# SmartSensorWifi.net
KiCad netlist of a schematic drawn in EAGLE
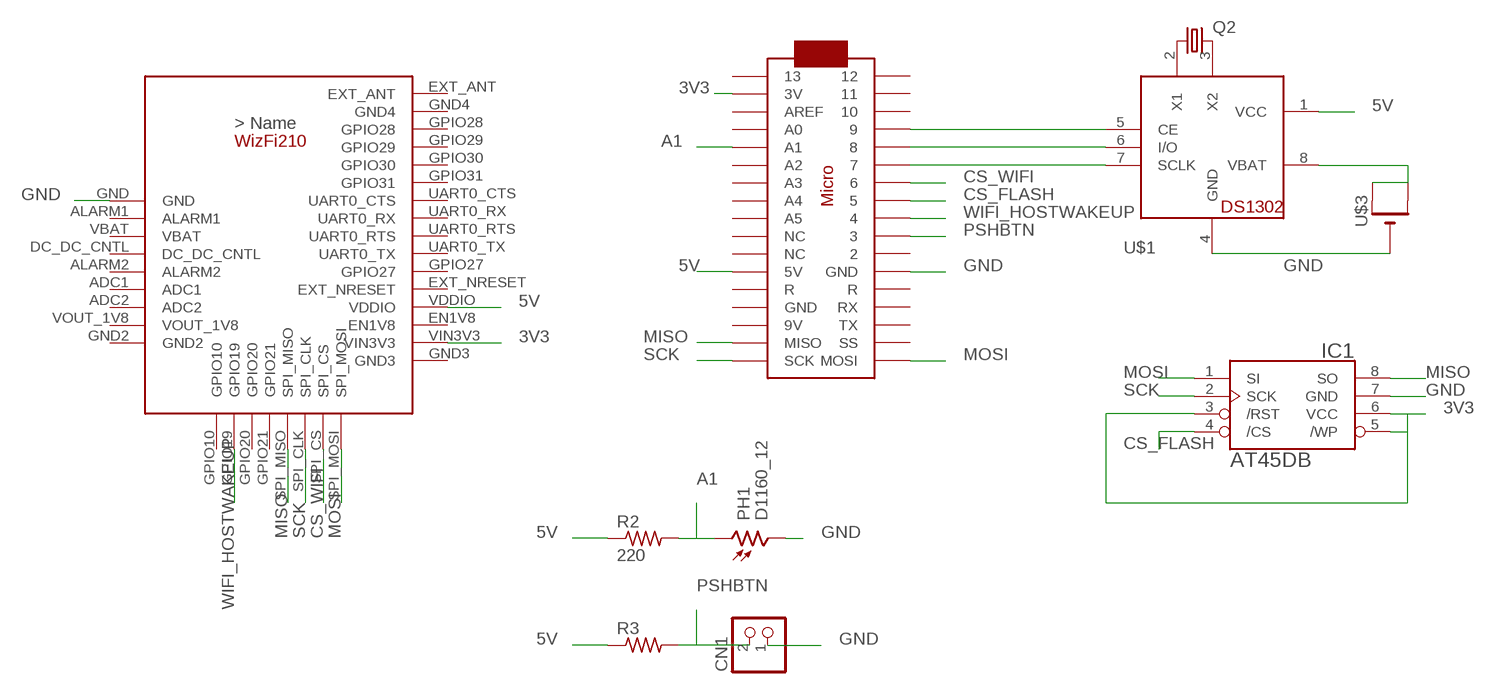
[diagram p0: schematic, sheet 1]

(export (version "E")
  (design (tool "Eeschema 10.0.6"))
  (components
    (comp (ref "CN1")
      (value "JST_2PIN-THM")
      (footprint "eagle-import:JST-PH-2-THM")
      (libsource (lib "eagle-import") (part "JST_2PIN-THM"))
    )
    (comp (ref "IC1")
      (value "AT45DB-S")
      (footprint "eagle-import:SOIC8_208MIL")
      (libsource (lib "eagle-import") (part "AT45DB-S"))
    )
    (comp (ref "PH1")
      (value "D1160_12")
      (footprint "eagle-import:D11XX")
      (libsource (lib "eagle-import") (part "D1160_12"))
    )
    (comp (ref "Q2")
      (value "CRYSTALTC38H")
      (footprint "eagle-import:TC38H")
      (libsource (lib "eagle-import") (part "CRYSTALTC38H"))
    )
    (comp (ref "R2")
      (value "220")
      (footprint "eagle-import:0207_12")
      (libsource (lib "eagle-import") (part "R-US_0207/12"))
    )
    (comp (ref "R3")
      (value "R-US_0207/12")
      (footprint "eagle-import:0207_12")
      (libsource (lib "eagle-import") (part "R-US_0207/12"))
    )
    (comp (ref "U$1")
      (value "DS1302")
      (footprint "eagle-import:DIL08-ROUND")
      (libsource (lib "eagle-import") (part "DS1302"))
    )
    (comp (ref "U$2")
      (value "ARDUINOMICRO")
      (footprint "eagle-import:ARDUINOMICRO")
      (libsource (lib "eagle-import") (part "ARDUINOMICRO"))
    )
    (comp (ref "U$3")
      (value "CR2032THM")
      (footprint "eagle-import:CR2032-THRU")
      (libsource (lib "eagle-import") (part "CR2032THM"))
    )
    (comp (ref "U$4")
      (value "WIZFISTACKED")
      (footprint "eagle-import:WIZFI210STACKABLE")
      (libsource (lib "eagle-import") (part "WIZFISTACKED"))
    )
  )
  (nets
    (net (code "1") (name "/3V3") (class "Default")
      (node (ref "IC1") (pin "3") (pinfunction "/RST_3") (pintype "input"))
      (node (ref "IC1") (pin "5") (pinfunction "/WP_5") (pintype "input"))
      (node (ref "IC1") (pin "6") (pinfunction "VCC_6") (pintype "power_in"))
      (node (ref "U$2") (pin "P$33") (pinfunction "3V_P$33") (pintype "bidirectional"))
      (node (ref "U$4") (pin "VIN3V3") (pinfunction "VIN3V3_VIN3V3") (pintype "power_in"))
    )
    (net (code "2") (name "/5V") (class "Default")
      (node (ref "R2") (pin "1") (pinfunction "1_1") (pintype "passive"))
      (node (ref "R3") (pin "1") (pinfunction "1_1") (pintype "passive"))
      (node (ref "U$1") (pin "1") (pinfunction "VCC_1") (pintype "power_in"))
      (node (ref "U$2") (pin "P$23") (pinfunction "5V_P$23") (pintype "bidirectional"))
      (node (ref "U$4") (pin "VDDIO") (pinfunction "VDDIO_VDDIO") (pintype "bidirectional"))
    )
    (net (code "3") (name "/A1") (class "Default")
      (node (ref "PH1") (pin "1") (pinfunction "1_1") (pintype "passive"))
      (node (ref "R2") (pin "2") (pinfunction "2_2") (pintype "passive"))
      (node (ref "U$2") (pin "P$30") (pinfunction "A1_P$30") (pintype "bidirectional"))
    )
    (net (code "4") (name "/CS_FLASH") (class "Default")
      (node (ref "IC1") (pin "4") (pinfunction "/CS_4") (pintype "input"))
      (node (ref "U$2") (pin "P$8") (pinfunction "5_P$8") (pintype "bidirectional"))
    )
    (net (code "5") (name "/CS_WIFI") (class "Default")
      (node (ref "U$2") (pin "P$7") (pinfunction "6_P$7") (pintype "bidirectional"))
      (node (ref "U$4") (pin "SPI_CS") (pinfunction "SPI_CS_SPI_CS") (pintype "input"))
    )
    (net (code "6") (name "/GND") (class "Default")
      (node (ref "CN1") (pin "1") (pinfunction "2_1") (pintype "passive"))
      (node (ref "IC1") (pin "7") (pinfunction "GND_7") (pintype "power_in"))
      (node (ref "PH1") (pin "2") (pinfunction "2_2") (pintype "passive"))
      (node (ref "U$1") (pin "4") (pinfunction "GND_4") (pintype "power_in"))
      (node (ref "U$2") (pin "P$21") (pinfunction "GND_P$21") (pintype "bidirectional"))
      (node (ref "U$3") (pin "-") (pinfunction "-_-") (pintype "passive"))
      (node (ref "U$4") (pin "GND") (pinfunction "GND_GND") (pintype "power_in"))
    )
    (net (code "7") (name "/GND2") (class "Default")
      (node (ref "U$4") (pin "GND2") (pinfunction "GND2_GND2") (pintype "power_in"))
    )
    (net (code "8") (name "/GND3") (class "Default")
      (node (ref "U$4") (pin "GND3") (pinfunction "GND3_GND3") (pintype "power_in"))
    )
    (net (code "9") (name "/GND4") (class "Default")
      (node (ref "U$4") (pin "GND4") (pinfunction "GND4_GND4") (pintype "power_in"))
    )
    (net (code "10") (name "/MISO") (class "Default")
      (node (ref "IC1") (pin "8") (pinfunction "SO_8") (pintype "output"))
      (node (ref "U$2") (pin "P$19") (pinfunction "MISO_P$19") (pintype "bidirectional"))
      (node (ref "U$4") (pin "SPI_MISO") (pinfunction "SPI_MISO_SPI_MISO") (pintype "output"))
    )
    (net (code "11") (name "/MOSI") (class "Default")
      (node (ref "IC1") (pin "1") (pinfunction "SI_1") (pintype "input"))
      (node (ref "U$2") (pin "P$17") (pinfunction "MOSI_P$17") (pintype "bidirectional"))
      (node (ref "U$4") (pin "SPI_MOSI") (pinfunction "SPI_MOSI_SPI_MOSI") (pintype "input"))
    )
    (net (code "12") (name "/PSHBTN") (class "Default")
      (node (ref "CN1") (pin "2") (pinfunction "1_2") (pintype "passive"))
      (node (ref "R3") (pin "2") (pinfunction "2_2") (pintype "passive"))
      (node (ref "U$2") (pin "P$10") (pinfunction "3_P$10") (pintype "bidirectional"))
    )
    (net (code "13") (name "/SCK") (class "Default")
      (node (ref "IC1") (pin "2") (pinfunction "SCK_2") (pintype "input"))
      (node (ref "U$2") (pin "P$18") (pinfunction "SCK_P$18") (pintype "bidirectional"))
      (node (ref "U$4") (pin "SPI_CLK") (pinfunction "SPI_CLK_SPI_CLK") (pintype "input"))
    )
    (net (code "14") (name "/VBAT") (class "Default")
      (node (ref "U$4") (pin "VBAT") (pinfunction "VBAT_VBAT") (pintype "power_in"))
    )
    (net (code "15") (name "/VOUT_1V8") (class "Default")
      (node (ref "U$4") (pin "VOUT_1V8") (pinfunction "VOUT_1V8_VOUT_1V8") (pintype "power_in"))
    )
    (net (code "16") (name "/WIFI_HOSTWAKEUP") (class "Default")
      (node (ref "U$2") (pin "P$9") (pinfunction "4_P$9") (pintype "bidirectional"))
      (node (ref "U$4") (pin "GPIO19") (pinfunction "GPIO19_GPIO19") (pintype "bidirectional"))
    )
    (net (code "17") (name "Net-(U$1-CE)") (class "Default")
      (node (ref "U$1") (pin "5") (pinfunction "CE_5") (pintype "input"))
      (node (ref "U$2") (pin "P$4") (pinfunction "9_P$4") (pintype "bidirectional"))
    )
    (net (code "18") (name "Net-(U$1-I{slash}O)") (class "Default")
      (node (ref "U$1") (pin "6") (pinfunction "I/O_6") (pintype "bidirectional"))
      (node (ref "U$2") (pin "P$5") (pinfunction "8_P$5") (pintype "bidirectional"))
    )
    (net (code "19") (name "Net-(U$1-SCLK)") (class "Default")
      (node (ref "U$1") (pin "7") (pinfunction "SCLK_7") (pintype "input"))
      (node (ref "U$2") (pin "P$6") (pinfunction "7_P$6") (pintype "bidirectional"))
    )
    (net (code "20") (name "Net-(U$1-VBAT)") (class "Default")
      (node (ref "U$1") (pin "8") (pinfunction "VBAT_8") (pintype "power_in"))
      (node (ref "U$3") (pin "+1") (pinfunction "+_+1") (pintype "passive"))
      (node (ref "U$3") (pin "+2") (pinfunction "+1_+2") (pintype "passive"))
    )
    (net (code "21") (name "Net-(U$1-X1)") (class "Default")
      (node (ref "Q2") (pin "1") (pinfunction "1_1") (pintype "passive"))
      (node (ref "U$1") (pin "2") (pinfunction "X1_2") (pintype "passive"))
    )
    (net (code "22") (name "Net-(U$1-X2)") (class "Default")
      (node (ref "Q2") (pin "2") (pinfunction "2_2") (pintype "passive"))
      (node (ref "U$1") (pin "3") (pinfunction "X2_3") (pintype "passive"))
    )
    (net (code "23") (name "unconnected-(U$2-2-PadP$11)") (class "Default")
      (node (ref "U$2") (pin "P$11") (pinfunction "2_P$11") (pintype "bidirectional"))
    )
    (net (code "24") (name "unconnected-(U$2-9V-PadP$20)") (class "Default")
      (node (ref "U$2") (pin "P$20") (pinfunction "9V_P$20") (pintype "bidirectional"))
    )
    (net (code "25") (name "unconnected-(U$2-10-PadP$3)") (class "Default")
      (node (ref "U$2") (pin "P$3") (pinfunction "10_P$3") (pintype "bidirectional"))
    )
    (net (code "26") (name "unconnected-(U$2-11-PadP$2)") (class "Default")
      (node (ref "U$2") (pin "P$2") (pinfunction "11_P$2") (pintype "bidirectional"))
    )
    (net (code "27") (name "unconnected-(U$2-12-PadP$1)") (class "Default")
      (node (ref "U$2") (pin "P$1") (pinfunction "12_P$1") (pintype "bidirectional"))
    )
    (net (code "28") (name "unconnected-(U$2-13-PadP$34)") (class "Default")
      (node (ref "U$2") (pin "P$34") (pinfunction "13_P$34") (pintype "bidirectional"))
    )
    (net (code "29") (name "unconnected-(U$2-A0-PadP$31)") (class "Default")
      (node (ref "U$2") (pin "P$31") (pinfunction "A0_P$31") (pintype "bidirectional"))
    )
    (net (code "30") (name "unconnected-(U$2-A2-PadP$29)") (class "Default")
      (node (ref "U$2") (pin "P$29") (pinfunction "A2_P$29") (pintype "bidirectional"))
    )
    (net (code "31") (name "unconnected-(U$2-A3-PadP$28)") (class "Default")
      (node (ref "U$2") (pin "P$28") (pinfunction "A3_P$28") (pintype "bidirectional"))
    )
    (net (code "32") (name "unconnected-(U$2-A4-PadP$27)") (class "Default")
      (node (ref "U$2") (pin "P$27") (pinfunction "A4_P$27") (pintype "bidirectional"))
    )
    (net (code "33") (name "unconnected-(U$2-A5-PadP$26)") (class "Default")
      (node (ref "U$2") (pin "P$26") (pinfunction "A5_P$26") (pintype "bidirectional"))
    )
    (net (code "34") (name "unconnected-(U$2-AREF-PadP$32)") (class "Default")
      (node (ref "U$2") (pin "P$32") (pinfunction "AREF_P$32") (pintype "bidirectional"))
    )
    (net (code "35") (name "unconnected-(U$2-GND-PadP$12)") (class "Default")
      (node (ref "U$2") (pin "P$12") (pinfunction "GND_P$12") (pintype "bidirectional"))
    )
    (net (code "36") (name "unconnected-(U$2-NC-PadP$24)") (class "Default")
      (node (ref "U$2") (pin "P$24") (pinfunction "NC_P$24") (pintype "bidirectional"))
    )
    (net (code "37") (name "unconnected-(U$2-NC-PadP$25)") (class "Default")
      (node (ref "U$2") (pin "P$25") (pinfunction "NC_P$25") (pintype "bidirectional"))
    )
    (net (code "38") (name "unconnected-(U$2-R-PadP$13)") (class "Default")
      (node (ref "U$2") (pin "P$13") (pinfunction "R_P$13") (pintype "bidirectional"))
    )
    (net (code "39") (name "unconnected-(U$2-R-PadP$22)") (class "Default")
      (node (ref "U$2") (pin "P$22") (pinfunction "R_P$22") (pintype "bidirectional"))
    )
    (net (code "40") (name "unconnected-(U$2-RX-PadP$14)") (class "Default")
      (node (ref "U$2") (pin "P$14") (pinfunction "RX_P$14") (pintype "bidirectional"))
    )
    (net (code "41") (name "unconnected-(U$2-SS-PadP$16)") (class "Default")
      (node (ref "U$2") (pin "P$16") (pinfunction "SS_P$16") (pintype "bidirectional"))
    )
    (net (code "42") (name "unconnected-(U$2-TX-PadP$15)") (class "Default")
      (node (ref "U$2") (pin "P$15") (pinfunction "TX_P$15") (pintype "bidirectional"))
    )
    (net (code "43") (name "unconnected-(U$4-PadADC1)") (class "Default")
      (node (ref "U$4") (pin "ADC1") (pinfunction "ADC1_ADC1") (pintype "input"))
    )
    (net (code "44") (name "unconnected-(U$4-PadADC2)") (class "Default")
      (node (ref "U$4") (pin "ADC2") (pinfunction "ADC2_ADC2") (pintype "input"))
    )
    (net (code "45") (name "unconnected-(U$4-PadALARM1)") (class "Default")
      (node (ref "U$4") (pin "ALARM1") (pinfunction "ALARM1_ALARM1") (pintype "input"))
    )
    (net (code "46") (name "unconnected-(U$4-PadALARM2)") (class "Default")
      (node (ref "U$4") (pin "ALARM2") (pinfunction "ALARM2_ALARM2") (pintype "bidirectional"))
    )
    (net (code "47") (name "unconnected-(U$4-PadDC_DC_CNTL)") (class "Default")
      (node (ref "U$4") (pin "DC_DC_CNTL") (pinfunction "DC_DC_CNTL_DC_DC_CNTL") (pintype "output"))
    )
    (net (code "48") (name "unconnected-(U$4-PadEN1V8)") (class "Default")
      (node (ref "U$4") (pin "EN1V8") (pinfunction "EN1V8_EN1V8") (pintype "bidirectional"))
    )
    (net (code "49") (name "unconnected-(U$4-PadEXT_ANT)") (class "Default")
      (node (ref "U$4") (pin "EXT_ANT") (pinfunction "EXT_ANT_EXT_ANT") (pintype "bidirectional"))
    )
    (net (code "50") (name "unconnected-(U$4-PadEXT_NRESET)") (class "Default")
      (node (ref "U$4") (pin "EXT_NRESET") (pinfunction "EXT_NRESET_EXT_NRESET") (pintype "bidirectional"))
    )
    (net (code "51") (name "unconnected-(U$4-PadGPIO10)") (class "Default")
      (node (ref "U$4") (pin "GPIO10") (pinfunction "GPIO10_GPIO10") (pintype "bidirectional"))
    )
    (net (code "52") (name "unconnected-(U$4-PadGPIO20)") (class "Default")
      (node (ref "U$4") (pin "GPIO20") (pinfunction "GPIO20_GPIO20") (pintype "bidirectional"))
    )
    (net (code "53") (name "unconnected-(U$4-PadGPIO21)") (class "Default")
      (node (ref "U$4") (pin "GPIO21") (pinfunction "GPIO21_GPIO21") (pintype "bidirectional"))
    )
    (net (code "54") (name "unconnected-(U$4-PadGPIO27)") (class "Default")
      (node (ref "U$4") (pin "GPIO27") (pinfunction "GPIO27_GPIO27") (pintype "bidirectional"))
    )
    (net (code "55") (name "unconnected-(U$4-PadGPIO28)") (class "Default")
      (node (ref "U$4") (pin "GPIO28") (pinfunction "GPIO28_GPIO28") (pintype "bidirectional"))
    )
    (net (code "56") (name "unconnected-(U$4-PadGPIO29)") (class "Default")
      (node (ref "U$4") (pin "GPIO29") (pinfunction "GPIO29_GPIO29") (pintype "bidirectional"))
    )
    (net (code "57") (name "unconnected-(U$4-PadGPIO30)") (class "Default")
      (node (ref "U$4") (pin "GPIO30") (pinfunction "GPIO30_GPIO30") (pintype "bidirectional"))
    )
    (net (code "58") (name "unconnected-(U$4-PadGPIO31)") (class "Default")
      (node (ref "U$4") (pin "GPIO31") (pinfunction "GPIO31_GPIO31") (pintype "bidirectional"))
    )
    (net (code "59") (name "unconnected-(U$4-PadUART0_CTS)") (class "Default")
      (node (ref "U$4") (pin "UART0_CTS") (pinfunction "UART0_CTS_UART0_CTS") (pintype "bidirectional"))
    )
    (net (code "60") (name "unconnected-(U$4-PadUART0_RTS)") (class "Default")
      (node (ref "U$4") (pin "UART0_RTS") (pinfunction "UART0_RTS_UART0_RTS") (pintype "bidirectional"))
    )
    (net (code "61") (name "unconnected-(U$4-PadUART0_RX)") (class "Default")
      (node (ref "U$4") (pin "UART0_RX") (pinfunction "UART0_RX_UART0_RX") (pintype "bidirectional"))
    )
    (net (code "62") (name "unconnected-(U$4-PadUART0_TX)") (class "Default")
      (node (ref "U$4") (pin "UART0_TX") (pinfunction "UART0_TX_UART0_TX") (pintype "bidirectional"))
    )
  )
)
